# DronePoles.net
KiCad netlist of a schematic drawn in EAGLE
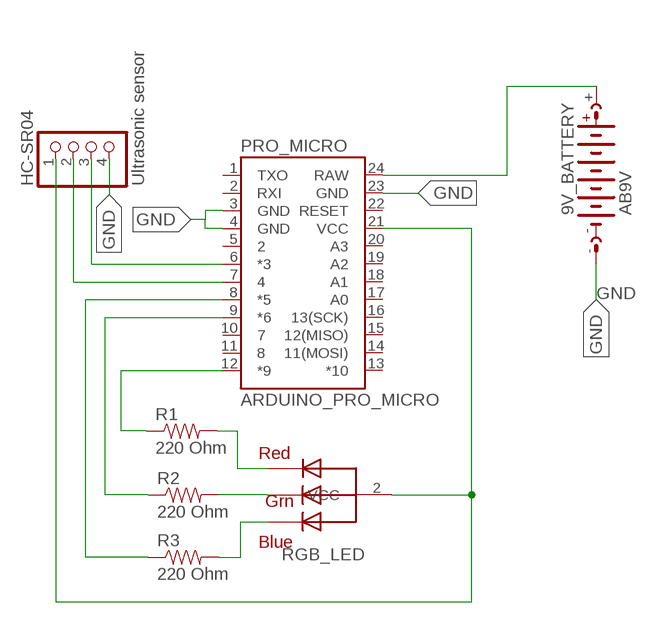
[diagram p0: schematic, sheet 1]

(export (version "E")
  (design (tool "Eeschema 10.0.6"))
  (components
    (comp (ref "9V_BATTERY")
      (value "AB9V")
      (footprint "eagle-import:AB9V")
      (libsource (lib "eagle-import") (part "AB9V"))
    )
    (comp (ref "HC-SR04")
      (value "Ultrasonic sensor")
      (footprint "eagle-import:1X04")
      (libsource (lib "eagle-import") (part "PINHD-1X4"))
    )
    (comp (ref "PRO_MICRO")
      (value "ARDUINO_PRO_MICRO")
      (footprint "eagle-import:ARDUINO_PRO_MICRO")
      (libsource (lib "eagle-import") (part "ARDUINO_PRO_MICRO"))
    )
    (comp (ref "R1")
      (value "220 Ohm")
      (footprint "eagle-import:AXIAL-0.3")
      (libsource (lib "eagle-import") (part "RESISTORAXIAL-0.3"))
    )
    (comp (ref "R2")
      (value "220 Ohm")
      (footprint "eagle-import:AXIAL-0.3")
      (libsource (lib "eagle-import") (part "RESISTORAXIAL-0.3"))
    )
    (comp (ref "R3")
      (value "220 Ohm")
      (footprint "eagle-import:AXIAL-0.3")
      (libsource (lib "eagle-import") (part "RESISTORAXIAL-0.3"))
    )
    (comp (ref "RGB_LED")
      (value "RGBLED_CA")
      (footprint "eagle-import:LED5MMRGB")
      (libsource (lib "eagle-import") (part "RGBLED_CA"))
    )
  )
  (nets
    (net (code "1") (name "GND") (class "Default")
      (node (ref "9V_BATTERY") (pin "-") (pinfunction "-_-") (pintype "passive"))
      (node (ref "HC-SR04") (pin "4") (pinfunction "4_4") (pintype "passive"))
      (node (ref "PRO_MICRO") (pin "23") (pinfunction "GND_23") (pintype "bidirectional"))
      (node (ref "PRO_MICRO") (pin "3") (pinfunction "GND_3") (pintype "bidirectional"))
      (node (ref "PRO_MICRO") (pin "4") (pinfunction "GND_4") (pintype "bidirectional"))
    )
    (net (code "2") (name "Net-(PRO_MICRO-*3)") (class "Default")
      (node (ref "HC-SR04") (pin "3") (pinfunction "3_3") (pintype "passive"))
      (node (ref "PRO_MICRO") (pin "6") (pinfunction "*3_6") (pintype "bidirectional"))
    )
    (net (code "3") (name "Net-(PRO_MICRO-*5)") (class "Default")
      (node (ref "PRO_MICRO") (pin "8") (pinfunction "*5_8") (pintype "bidirectional"))
      (node (ref "R3") (pin "P$1") (pinfunction "1_P$1") (pintype "passive"))
    )
    (net (code "4") (name "Net-(PRO_MICRO-*6)") (class "Default")
      (node (ref "PRO_MICRO") (pin "9") (pinfunction "*6_9") (pintype "bidirectional"))
      (node (ref "R2") (pin "P$1") (pinfunction "1_P$1") (pintype "passive"))
    )
    (net (code "5") (name "Net-(PRO_MICRO-*9)") (class "Default")
      (node (ref "PRO_MICRO") (pin "12") (pinfunction "*9_12") (pintype "bidirectional"))
      (node (ref "R1") (pin "P$1") (pinfunction "1_P$1") (pintype "passive"))
    )
    (net (code "6") (name "Net-(PRO_MICRO-4)") (class "Default")
      (node (ref "HC-SR04") (pin "2") (pinfunction "2_2") (pintype "passive"))
      (node (ref "PRO_MICRO") (pin "7") (pinfunction "4_7") (pintype "bidirectional"))
    )
    (net (code "7") (name "Net-(PRO_MICRO-RAW)") (class "Default")
      (node (ref "9V_BATTERY") (pin "+") (pinfunction "+_+") (pintype "passive"))
      (node (ref "PRO_MICRO") (pin "24") (pinfunction "RAW_24") (pintype "bidirectional"))
    )
    (net (code "8") (name "Net-(PRO_MICRO-VCC)") (class "Default")
      (node (ref "HC-SR04") (pin "1") (pinfunction "1_1") (pintype "passive"))
      (node (ref "PRO_MICRO") (pin "21") (pinfunction "VCC_21") (pintype "bidirectional"))
      (node (ref "RGB_LED") (pin "2") (pinfunction "VCC_2") (pintype "bidirectional"))
    )
    (net (code "9") (name "Net-(R1-2)") (class "Default")
      (node (ref "R1") (pin "P$2") (pinfunction "2_P$2") (pintype "passive"))
      (node (ref "RGB_LED") (pin "1") (pinfunction "RED_1") (pintype "bidirectional"))
    )
    (net (code "10") (name "Net-(R2-2)") (class "Default")
      (node (ref "R2") (pin "P$2") (pinfunction "2_P$2") (pintype "passive"))
      (node (ref "RGB_LED") (pin "3") (pinfunction "GREEN_3") (pintype "bidirectional"))
    )
    (net (code "11") (name "Net-(R3-2)") (class "Default")
      (node (ref "R3") (pin "P$2") (pinfunction "2_P$2") (pintype "passive"))
      (node (ref "RGB_LED") (pin "4") (pinfunction "BLUE_4") (pintype "bidirectional"))
    )
    (net (code "12") (name "unconnected-(PRO_MICRO-*10-Pad13)") (class "Default")
      (node (ref "PRO_MICRO") (pin "13") (pinfunction "*10_13") (pintype "bidirectional"))
    )
    (net (code "13") (name "unconnected-(PRO_MICRO-2-Pad5)") (class "Default")
      (node (ref "PRO_MICRO") (pin "5") (pinfunction "2_5") (pintype "bidirectional"))
    )
    (net (code "14") (name "unconnected-(PRO_MICRO-7-Pad10)") (class "Default")
      (node (ref "PRO_MICRO") (pin "10") (pinfunction "7_10") (pintype "bidirectional"))
    )
    (net (code "15") (name "unconnected-(PRO_MICRO-8-Pad11)") (class "Default")
      (node (ref "PRO_MICRO") (pin "11") (pinfunction "8_11") (pintype "bidirectional"))
    )
    (net (code "16") (name "unconnected-(PRO_MICRO-11(MOSI)-Pad14)") (class "Default")
      (node (ref "PRO_MICRO") (pin "14") (pinfunction "11(MOSI)_14") (pintype "bidirectional"))
    )
    (net (code "17") (name "unconnected-(PRO_MICRO-12(MISO)-Pad15)") (class "Default")
      (node (ref "PRO_MICRO") (pin "15") (pinfunction "12(MISO)_15") (pintype "bidirectional"))
    )
    (net (code "18") (name "unconnected-(PRO_MICRO-13(SCK)-Pad16)") (class "Default")
      (node (ref "PRO_MICRO") (pin "16") (pinfunction "13(SCK)_16") (pintype "bidirectional"))
    )
    (net (code "19") (name "unconnected-(PRO_MICRO-A0-Pad17)") (class "Default")
      (node (ref "PRO_MICRO") (pin "17") (pinfunction "A0_17") (pintype "bidirectional"))
    )
    (net (code "20") (name "unconnected-(PRO_MICRO-A1-Pad18)") (class "Default")
      (node (ref "PRO_MICRO") (pin "18") (pinfunction "A1_18") (pintype "bidirectional"))
    )
    (net (code "21") (name "unconnected-(PRO_MICRO-A2-Pad19)") (class "Default")
      (node (ref "PRO_MICRO") (pin "19") (pinfunction "A2_19") (pintype "bidirectional"))
    )
    (net (code "22") (name "unconnected-(PRO_MICRO-A3-Pad20)") (class "Default")
      (node (ref "PRO_MICRO") (pin "20") (pinfunction "A3_20") (pintype "bidirectional"))
    )
    (net (code "23") (name "unconnected-(PRO_MICRO-RESET-Pad22)") (class "Default")
      (node (ref "PRO_MICRO") (pin "22") (pinfunction "RESET_22") (pintype "bidirectional"))
    )
    (net (code "24") (name "unconnected-(PRO_MICRO-RXI-Pad2)") (class "Default")
      (node (ref "PRO_MICRO") (pin "2") (pinfunction "RXI_2") (pintype "bidirectional"))
    )
    (net (code "25") (name "unconnected-(PRO_MICRO-TXO-Pad1)") (class "Default")
      (node (ref "PRO_MICRO") (pin "1") (pinfunction "TXO_1") (pintype "bidirectional"))
    )
  )
)
